# working.net
KiCad netlist of a schematic drawn in EAGLE
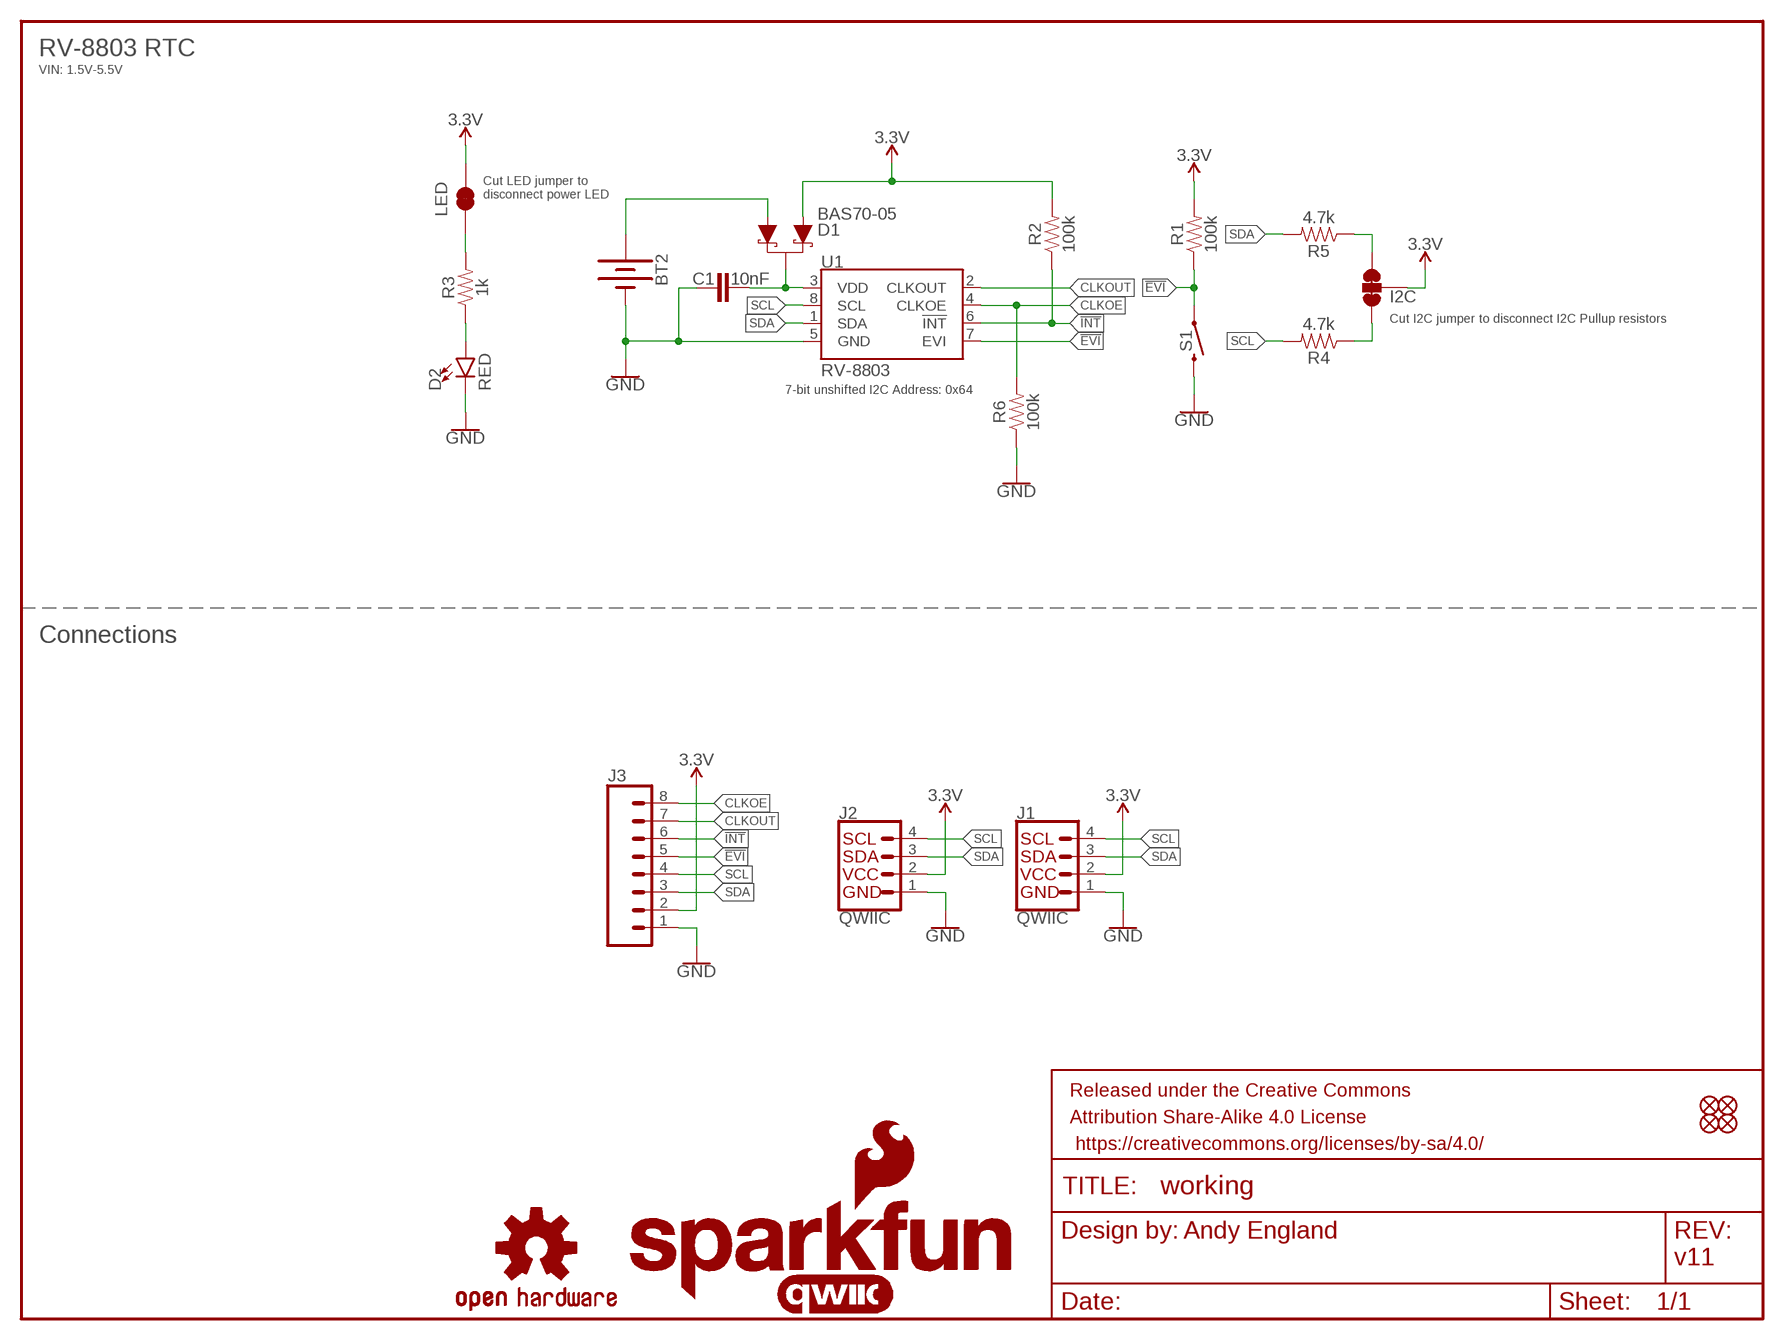
[diagram p0: schematic, sheet 1]

(export (version "E")
  (design (tool "Eeschema 10.0.6"))
  (components
    (comp (ref "BT2")
      (value "BATTERY-12MM_SMD")
      (footprint "eagle-import:BATTCON_12MM")
      (libsource (lib "eagle-import") (part "BATTERY-12MM_SMD"))
    )
    (comp (ref "C1")
      (value "10nF")
      (footprint "eagle-import:0603")
      (libsource (lib "eagle-import") (part "10NF-0603-50V-10%"))
    )
    (comp (ref "D1")
      (value "BAS70-05")
      (footprint "eagle-import:SOT23-3")
      (libsource (lib "eagle-import") (part "DIODE-SCHOTTKY-DUAL"))
    )
    (comp (ref "D2")
      (value "RED")
      (footprint "eagle-import:LED-0603")
      (libsource (lib "eagle-import") (part "LED-RED0603"))
    )
    (comp (ref "FD1")
      (value "FIDUCIALUFIDUCIAL")
      (footprint "eagle-import:FIDUCIAL-MICRO")
      (libsource (lib "eagle-import") (part "FIDUCIALUFIDUCIAL"))
    )
    (comp (ref "FD2")
      (value "FIDUCIALUFIDUCIAL")
      (footprint "eagle-import:FIDUCIAL-MICRO")
      (libsource (lib "eagle-import") (part "FIDUCIALUFIDUCIAL"))
    )
    (comp (ref "FD3")
      (value "FIDUCIALUFIDUCIAL")
      (footprint "eagle-import:FIDUCIAL-MICRO")
      (libsource (lib "eagle-import") (part "FIDUCIALUFIDUCIAL"))
    )
    (comp (ref "FD4")
      (value "FIDUCIALUFIDUCIAL")
      (footprint "eagle-import:FIDUCIAL-MICRO")
      (libsource (lib "eagle-import") (part "FIDUCIALUFIDUCIAL"))
    )
    (comp (ref "FRAME1")
      (value "FRAME-LETTER")
      (footprint "eagle-import:CREATIVE_COMMONS")
      (libsource (lib "eagle-import") (part "FRAME-LETTER"))
    )
    (comp (ref "I2C")
      (value "JUMPER-SMT_3_2-NC_TRACE_NO-SILK")
      (footprint "eagle-import:SMT-JUMPER_3_2-NC_TRACE_NO-SILK")
      (libsource (lib "eagle-import") (part "JUMPER-SMT_3_2-NC_TRACE_NO-SILK"))
    )
    (comp (ref "J1")
      (value "QWIIC")
      (footprint "eagle-import:JST04_1MM_RA")
      (libsource (lib "eagle-import") (part "QWIIC_CONNECTORJS-1MM"))
    )
    (comp (ref "J2")
      (value "QWIIC")
      (footprint "eagle-import:JST04_1MM_RA")
      (libsource (lib "eagle-import") (part "QWIIC_CONNECTORJS-1MM"))
    )
    (comp (ref "J3")
      (value "CONN_08NO_SILK_FEMALE_PTH")
      (footprint "eagle-import:1X08_NO_SILK")
      (libsource (lib "eagle-import") (part "CONN_08NO_SILK_FEMALE_PTH"))
    )
    (comp (ref "LED")
      (value "JUMPER-SMT_2_NC_TRACE_NO-SILK")
      (footprint "eagle-import:SMT-JUMPER_2_NC_TRACE_NO-SILK")
      (libsource (lib "eagle-import") (part "JUMPER-SMT_2_NC_TRACE_NO-SILK"))
    )
    (comp (ref "LOGO1")
      (value "SFE_LOGO_NAME_FLAME.1_INCH")
      (footprint "eagle-import:SFE_LOGO_NAME_FLAME_.1")
      (libsource (lib "eagle-import") (part "SFE_LOGO_NAME_FLAME.1_INCH"))
    )
    (comp (ref "LOGO2")
      (value "OSHW-LOGOS")
      (footprint "eagle-import:OSHW-LOGO-S")
      (libsource (lib "eagle-import") (part "OSHW-LOGOS"))
    )
    (comp (ref "LOGO4")
      (value "QWIIC_LOGO_5MM")
      (footprint "eagle-import:QWIIC_5MM")
      (libsource (lib "eagle-import") (part "QWIIC_LOGO_5MM"))
    )
    (comp (ref "LOGO5")
      (value "SFE_LOGO_NAME.1_INCH")
      (footprint "eagle-import:SFE_LOGO_NAME_.1")
      (libsource (lib "eagle-import") (part "SFE_LOGO_NAME.1_INCH"))
    )
    (comp (ref "R1")
      (value "100k")
      (footprint "eagle-import:0603")
      (libsource (lib "eagle-import") (part "100KOHM-0603-1/10W-1%"))
    )
    (comp (ref "R2")
      (value "100k")
      (footprint "eagle-import:0603")
      (libsource (lib "eagle-import") (part "100KOHM-0603-1/10W-1%"))
    )
    (comp (ref "R3")
      (value "1k")
      (footprint "eagle-import:0603")
      (libsource (lib "eagle-import") (part "1KOHM-0603-1/10W-1%"))
    )
    (comp (ref "R4")
      (value "4.7k")
      (footprint "eagle-import:0603")
      (libsource (lib "eagle-import") (part "4.7KOHM-0603-1/10W-1%"))
    )
    (comp (ref "R5")
      (value "4.7k")
      (footprint "eagle-import:0603")
      (libsource (lib "eagle-import") (part "4.7KOHM-0603-1/10W-1%"))
    )
    (comp (ref "R6")
      (value "100k")
      (footprint "eagle-import:0603")
      (libsource (lib "eagle-import") (part "100KOHM-0603-1/10W-1%"))
    )
    (comp (ref "S1")
      (value "MOMENTARY-SWITCH-SPST-SMD-5.2MM-TALL")
      (footprint "eagle-import:TACTILE_SWITCH_SMD_5.2MM")
      (libsource (lib "eagle-import") (part "MOMENTARY-SWITCH-SPST-SMD-5.2MM-TALL"))
    )
    (comp (ref "U1")
      (value "RV-8803")
      (footprint "eagle-import:RV-3028")
      (libsource (lib "eagle-import") (part "RV-8803"))
    )
  )
  (nets
    (net (code "1") (name "/~{EVI}") (class "Default")
      (node (ref "J3") (pin "5") (pinfunction "5_5") (pintype "passive"))
      (node (ref "R1") (pin "1") (pinfunction "1_1") (pintype "passive"))
      (node (ref "S1") (pin "1") (pinfunction "1_1") (pintype "passive"))
      (node (ref "U1") (pin "7") (pinfunction "EVI_7") (pintype "bidirectional"))
    )
    (net (code "2") (name "/~{INT}") (class "Default")
      (node (ref "J3") (pin "6") (pinfunction "6_6") (pintype "passive"))
      (node (ref "R2") (pin "1") (pinfunction "1_1") (pintype "passive"))
      (node (ref "U1") (pin "6") (pinfunction "~{INT}_6") (pintype "bidirectional"))
    )
    (net (code "3") (name "3.3V") (class "Default")
      (node (ref "D1") (pin "1") (pinfunction "A_1") (pintype "passive"))
      (node (ref "I2C") (pin "2") (pinfunction "2_2") (pintype "passive"))
      (node (ref "J1") (pin "2") (pinfunction "2_2") (pintype "power_in"))
      (node (ref "J2") (pin "2") (pinfunction "2_2") (pintype "power_in"))
      (node (ref "J3") (pin "2") (pinfunction "2_2") (pintype "passive"))
      (node (ref "LED") (pin "2") (pinfunction "2_2") (pintype "passive"))
      (node (ref "R1") (pin "2") (pinfunction "2_2") (pintype "passive"))
      (node (ref "R2") (pin "2") (pinfunction "2_2") (pintype "passive"))
    )
    (net (code "4") (name "CLKOE") (class "Default")
      (node (ref "J3") (pin "8") (pinfunction "8_8") (pintype "passive"))
      (node (ref "R6") (pin "2") (pinfunction "2_2") (pintype "passive"))
      (node (ref "U1") (pin "4") (pinfunction "CLKOE_4") (pintype "bidirectional"))
    )
    (net (code "5") (name "CLKOUT") (class "Default")
      (node (ref "J3") (pin "7") (pinfunction "7_7") (pintype "passive"))
      (node (ref "U1") (pin "2") (pinfunction "CLKOUT_2") (pintype "bidirectional"))
    )
    (net (code "6") (name "GND") (class "Default")
      (node (ref "BT2") (pin "GND") (pinfunction "-_GND") (pintype "power_in"))
      (node (ref "C1") (pin "1") (pinfunction "1_1") (pintype "passive"))
      (node (ref "D2") (pin "C") (pinfunction "C_C") (pintype "passive"))
      (node (ref "J1") (pin "1") (pinfunction "1_1") (pintype "power_in"))
      (node (ref "J2") (pin "1") (pinfunction "1_1") (pintype "power_in"))
      (node (ref "J3") (pin "1") (pinfunction "1_1") (pintype "passive"))
      (node (ref "R6") (pin "1") (pinfunction "1_1") (pintype "passive"))
      (node (ref "S1") (pin "3") (pinfunction "2_3") (pintype "passive"))
      (node (ref "U1") (pin "5") (pinfunction "GND_5") (pintype "bidirectional"))
    )
    (net (code "7") (name "Net-(BT2-+)") (class "Default")
      (node (ref "BT2") (pin "PWR@1") (pinfunction "+_PWR@1") (pintype "power_in"))
      (node (ref "D1") (pin "2") (pinfunction "A1_2") (pintype "passive"))
    )
    (net (code "8") (name "Net-(D1-C)") (class "Default")
      (node (ref "C1") (pin "2") (pinfunction "2_2") (pintype "passive"))
      (node (ref "D1") (pin "3") (pinfunction "C_3") (pintype "passive"))
      (node (ref "U1") (pin "3") (pinfunction "VDD_3") (pintype "bidirectional"))
    )
    (net (code "9") (name "Net-(D2-PadA)") (class "Default")
      (node (ref "D2") (pin "A") (pinfunction "A_A") (pintype "passive"))
      (node (ref "R3") (pin "1") (pinfunction "1_1") (pintype "passive"))
    )
    (net (code "10") (name "Net-(I2C-Pad1)") (class "Default")
      (node (ref "I2C") (pin "1") (pinfunction "1_1") (pintype "passive"))
      (node (ref "R4") (pin "1") (pinfunction "1_1") (pintype "passive"))
    )
    (net (code "11") (name "Net-(I2C-Pad3)") (class "Default")
      (node (ref "I2C") (pin "3") (pinfunction "3_3") (pintype "passive"))
      (node (ref "R5") (pin "1") (pinfunction "1_1") (pintype "passive"))
    )
    (net (code "12") (name "Net-(LED-Pad1)") (class "Default")
      (node (ref "LED") (pin "1") (pinfunction "1_1") (pintype "passive"))
      (node (ref "R3") (pin "2") (pinfunction "2_2") (pintype "passive"))
    )
    (net (code "13") (name "SCL") (class "Default")
      (node (ref "J1") (pin "4") (pinfunction "4_4") (pintype "passive"))
      (node (ref "J2") (pin "4") (pinfunction "4_4") (pintype "passive"))
      (node (ref "J3") (pin "4") (pinfunction "4_4") (pintype "passive"))
      (node (ref "R4") (pin "2") (pinfunction "2_2") (pintype "passive"))
      (node (ref "U1") (pin "8") (pinfunction "SCL_8") (pintype "bidirectional"))
    )
    (net (code "14") (name "SDA") (class "Default")
      (node (ref "J1") (pin "3") (pinfunction "3_3") (pintype "passive"))
      (node (ref "J2") (pin "3") (pinfunction "3_3") (pintype "passive"))
      (node (ref "J3") (pin "3") (pinfunction "3_3") (pintype "passive"))
      (node (ref "R5") (pin "2") (pinfunction "2_2") (pintype "passive"))
      (node (ref "U1") (pin "1") (pinfunction "SDA_1") (pintype "bidirectional"))
    )
  )
)
